# STM32_SPI.net
KiCad netlist of a schematic drawn in Altium Designer
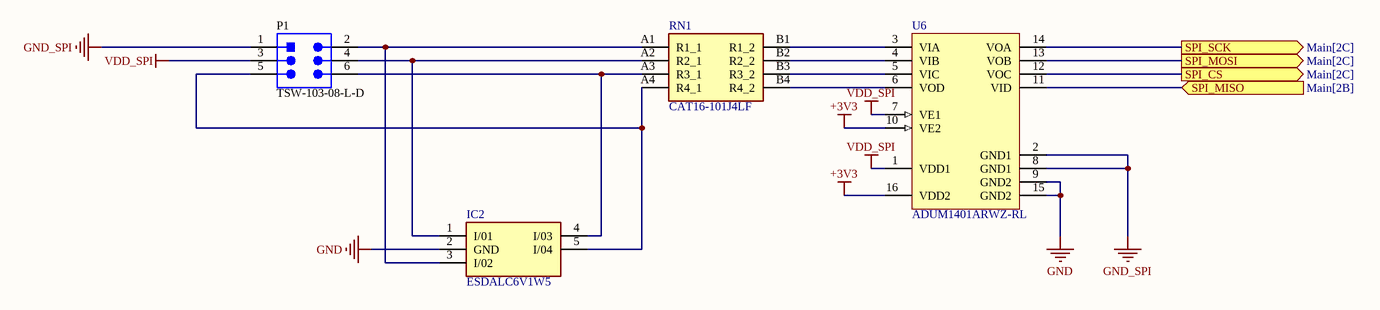
[diagram p0: STM32_SPI.SchDoc]

(export (version "E")
  (design (tool "Eeschema 10.0.6"))
  (components
    (comp (ref "IC2")
      (value "ESDALC6V1W5")
      (footprint "SamacSys:SOT65P210X110-5N")
      (description "Integrated Circuit")
      (fields (field (name "MOUSER PART NUMBER") "511-ESDALC6V1W5"))
      (libsource (lib "*") (part "ESDALC6V1W5"))
    )
    (comp (ref "P1")
      (value "TSW-103-08-L-D")
      (footprint "SMTC-TSW-103-08-L-D_V")
      (fields (field (name "MANUFACTURER") "Samtec"))
      (libsource (lib "Altium Content Vault") (part "CN-2P-M-R6"))
    )
    (comp (ref "RN1")
      (value "CAT16-101J4LF")
      (footprint "SamacSys:CAT16101J4LF")
      (description "Resistor Network")
      (fields (field (name "MOUSER PART NUMBER") "652-CAT16-101J4LF"))
      (libsource (lib "*") (part "CAT16-101J4LF"))
    )
    (comp (ref "U6")
      (value "ADUM1401ARWZ-RL")
      (footprint "ADI-RW-16_N")
      (fields (field (name "MANUFACTURER") "Analog Devices"))
      (libsource (lib "Altium Content Vault") (part "ADI-ADUMX4X1-16"))
    )
  )
  (nets
    (net (code "1") (name "+3V3") (class "Default")
      (node (ref "U6") (pin "10") (pinfunction "VE2_10") (pintype "input"))
      (node (ref "U6") (pin "16") (pinfunction "VDD2_16") (pintype "power_in"))
    )
    (net (code "2") (name "/SPI_CS") (class "Default")
      (node (ref "U6") (pin "12") (pinfunction "VOC_12") (pintype "tri_state"))
    )
    (net (code "3") (name "/SPI_MISO") (class "Default")
      (node (ref "U6") (pin "11") (pinfunction "VID_11") (pintype "passive"))
    )
    (net (code "4") (name "/SPI_MOSI") (class "Default")
      (node (ref "U6") (pin "13") (pinfunction "VOB_13") (pintype "tri_state"))
    )
    (net (code "5") (name "/SPI_SCK") (class "Default")
      (node (ref "U6") (pin "14") (pinfunction "VOA_14") (pintype "tri_state"))
    )
    (net (code "6") (name "GND") (class "Default")
      (node (ref "IC2") (pin "2") (pinfunction "GND_2") (pintype "passive"))
      (node (ref "U6") (pin "15") (pinfunction "GND2_15") (pintype "power_in"))
      (node (ref "U6") (pin "9") (pinfunction "GND2_9") (pintype "power_in"))
    )
    (net (code "7") (name "GND_SPI") (class "Default")
      (node (ref "P1") (pin "1") (pinfunction "1_1") (pintype "passive"))
      (node (ref "U6") (pin "2") (pinfunction "GND1_2") (pintype "power_in"))
      (node (ref "U6") (pin "8") (pinfunction "GND1_8") (pintype "power_in"))
    )
    (net (code "8") (name "Net-(IC2-I{slash}01)") (class "Default")
      (node (ref "IC2") (pin "1") (pinfunction "I/01_1") (pintype "passive"))
      (node (ref "P1") (pin "4") (pinfunction "4_4") (pintype "passive"))
      (node (ref "RN1") (pin "A2") (pinfunction "R2_1_A2") (pintype "passive"))
    )
    (net (code "9") (name "Net-(IC2-I{slash}02)") (class "Default")
      (node (ref "IC2") (pin "3") (pinfunction "I/02_3") (pintype "passive"))
      (node (ref "P1") (pin "2") (pinfunction "2_2") (pintype "passive"))
      (node (ref "RN1") (pin "A1") (pinfunction "R1_1_A1") (pintype "passive"))
    )
    (net (code "10") (name "Net-(IC2-I{slash}03)") (class "Default")
      (node (ref "IC2") (pin "4") (pinfunction "I/03_4") (pintype "passive"))
      (node (ref "P1") (pin "6") (pinfunction "6_6") (pintype "passive"))
      (node (ref "RN1") (pin "A3") (pinfunction "R3_1_A3") (pintype "passive"))
    )
    (net (code "11") (name "Net-(IC2-I{slash}04)") (class "Default")
      (node (ref "IC2") (pin "5") (pinfunction "I/04_5") (pintype "passive"))
      (node (ref "P1") (pin "5") (pinfunction "5_5") (pintype "passive"))
      (node (ref "RN1") (pin "A4") (pinfunction "R4_1_A4") (pintype "passive"))
    )
    (net (code "12") (name "Net-(RN1-R1_2)") (class "Default")
      (node (ref "RN1") (pin "B1") (pinfunction "R1_2_B1") (pintype "passive"))
      (node (ref "U6") (pin "3") (pinfunction "VIA_3") (pintype "passive"))
    )
    (net (code "13") (name "Net-(RN1-R2_2)") (class "Default")
      (node (ref "RN1") (pin "B2") (pinfunction "R2_2_B2") (pintype "passive"))
      (node (ref "U6") (pin "4") (pinfunction "VIB_4") (pintype "passive"))
    )
    (net (code "14") (name "Net-(RN1-R3_2)") (class "Default")
      (node (ref "RN1") (pin "B3") (pinfunction "R3_2_B3") (pintype "passive"))
      (node (ref "U6") (pin "5") (pinfunction "VIC_5") (pintype "passive"))
    )
    (net (code "15") (name "Net-(RN1-R4_2)") (class "Default")
      (node (ref "RN1") (pin "B4") (pinfunction "R4_2_B4") (pintype "passive"))
      (node (ref "U6") (pin "6") (pinfunction "VOD_6") (pintype "tri_state"))
    )
    (net (code "16") (name "VDD_SPI") (class "Default")
      (node (ref "P1") (pin "3") (pinfunction "3_3") (pintype "passive"))
      (node (ref "U6") (pin "1") (pinfunction "VDD1_1") (pintype "power_in"))
      (node (ref "U6") (pin "7") (pinfunction "VE1_7") (pintype "input"))
    )
  )
)
